# Sheet3.net
KiCad netlist of a schematic drawn in Altium Designer
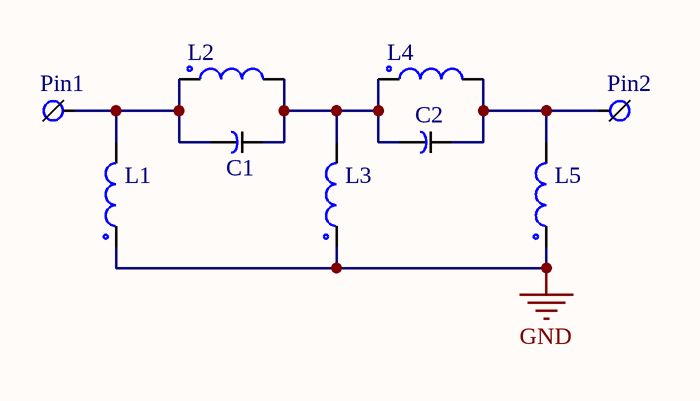
[diagram p0: Sheet3.SchDoc]

(export (version "E")
  (design (tool "Eeschema 10.0.6"))
  (components
    (comp (ref "C1") (value "C1") (footprint "C1") (libsource (lib "Schlib3") (part "C1")))
    (comp (ref "C2") (value "C2") (footprint "C2") (libsource (lib "Schlib3") (part "C2")))
    (comp (ref "L1") (value "L1,L5") (footprint "L1,L5") (libsource (lib "Schlib3") (part "L1,L5")))
    (comp (ref "L2") (value "L2,L4") (footprint "L2,L4") (libsource (lib "Schlib3") (part "L2,L4")))
    (comp (ref "L3") (value "L3") (footprint "L3") (libsource (lib "Schlib3") (part "L3")))
    (comp (ref "L4") (value "L2,L4") (footprint "L2,L4") (libsource (lib "Schlib3") (part "L2,L4")))
    (comp (ref "L5") (value "L1,L5") (footprint "L1,L5") (libsource (lib "Schlib3") (part "L1,L5")))
    (comp (ref "Pin1") (value "Pin") (footprint "Pin") (libsource (lib "Schlib3") (part "Pin")))
    (comp (ref "Pin2") (value "Pin") (footprint "Pin") (libsource (lib "Schlib3") (part "Pin")))
  )
  (nets
    (net (code "1") (name "GND") (class "Default")
      (node (ref "L1") (pin "1") (pinfunction "1_1") (pintype "passive"))
      (node (ref "L3") (pin "1") (pinfunction "1_1") (pintype "passive"))
      (node (ref "L5") (pin "1") (pinfunction "1_1") (pintype "passive"))
    )
    (net (code "2") (name "Net-(C1-Pad2)") (class "Default")
      (node (ref "C1") (pin "2") (pinfunction "2_2") (pintype "passive"))
      (node (ref "C2") (pin "1") (pinfunction "1_1") (pintype "passive"))
      (node (ref "L2") (pin "2") (pinfunction "2_2") (pintype "passive"))
      (node (ref "L3") (pin "2") (pinfunction "2_2") (pintype "passive"))
      (node (ref "L4") (pin "1") (pinfunction "1_1") (pintype "passive"))
    )
    (net (code "3") (name "Net-(Pin1-4)") (class "Default")
      (node (ref "C1") (pin "1") (pinfunction "1_1") (pintype "passive"))
      (node (ref "L1") (pin "2") (pinfunction "2_2") (pintype "passive"))
      (node (ref "L2") (pin "1") (pinfunction "1_1") (pintype "passive"))
      (node (ref "Pin1") (pin "1") (pinfunction "4_1") (pintype "passive"))
    )
    (net (code "4") (name "Net-(Pin2-4)") (class "Default")
      (node (ref "C2") (pin "2") (pinfunction "2_2") (pintype "passive"))
      (node (ref "L4") (pin "2") (pinfunction "2_2") (pintype "passive"))
      (node (ref "L5") (pin "2") (pinfunction "2_2") (pintype "passive"))
      (node (ref "Pin2") (pin "1") (pinfunction "4_1") (pintype "passive"))
    )
  )
)
